# RobotTraceStopWatch.net
KiCad netlist of a schematic drawn in EAGLE
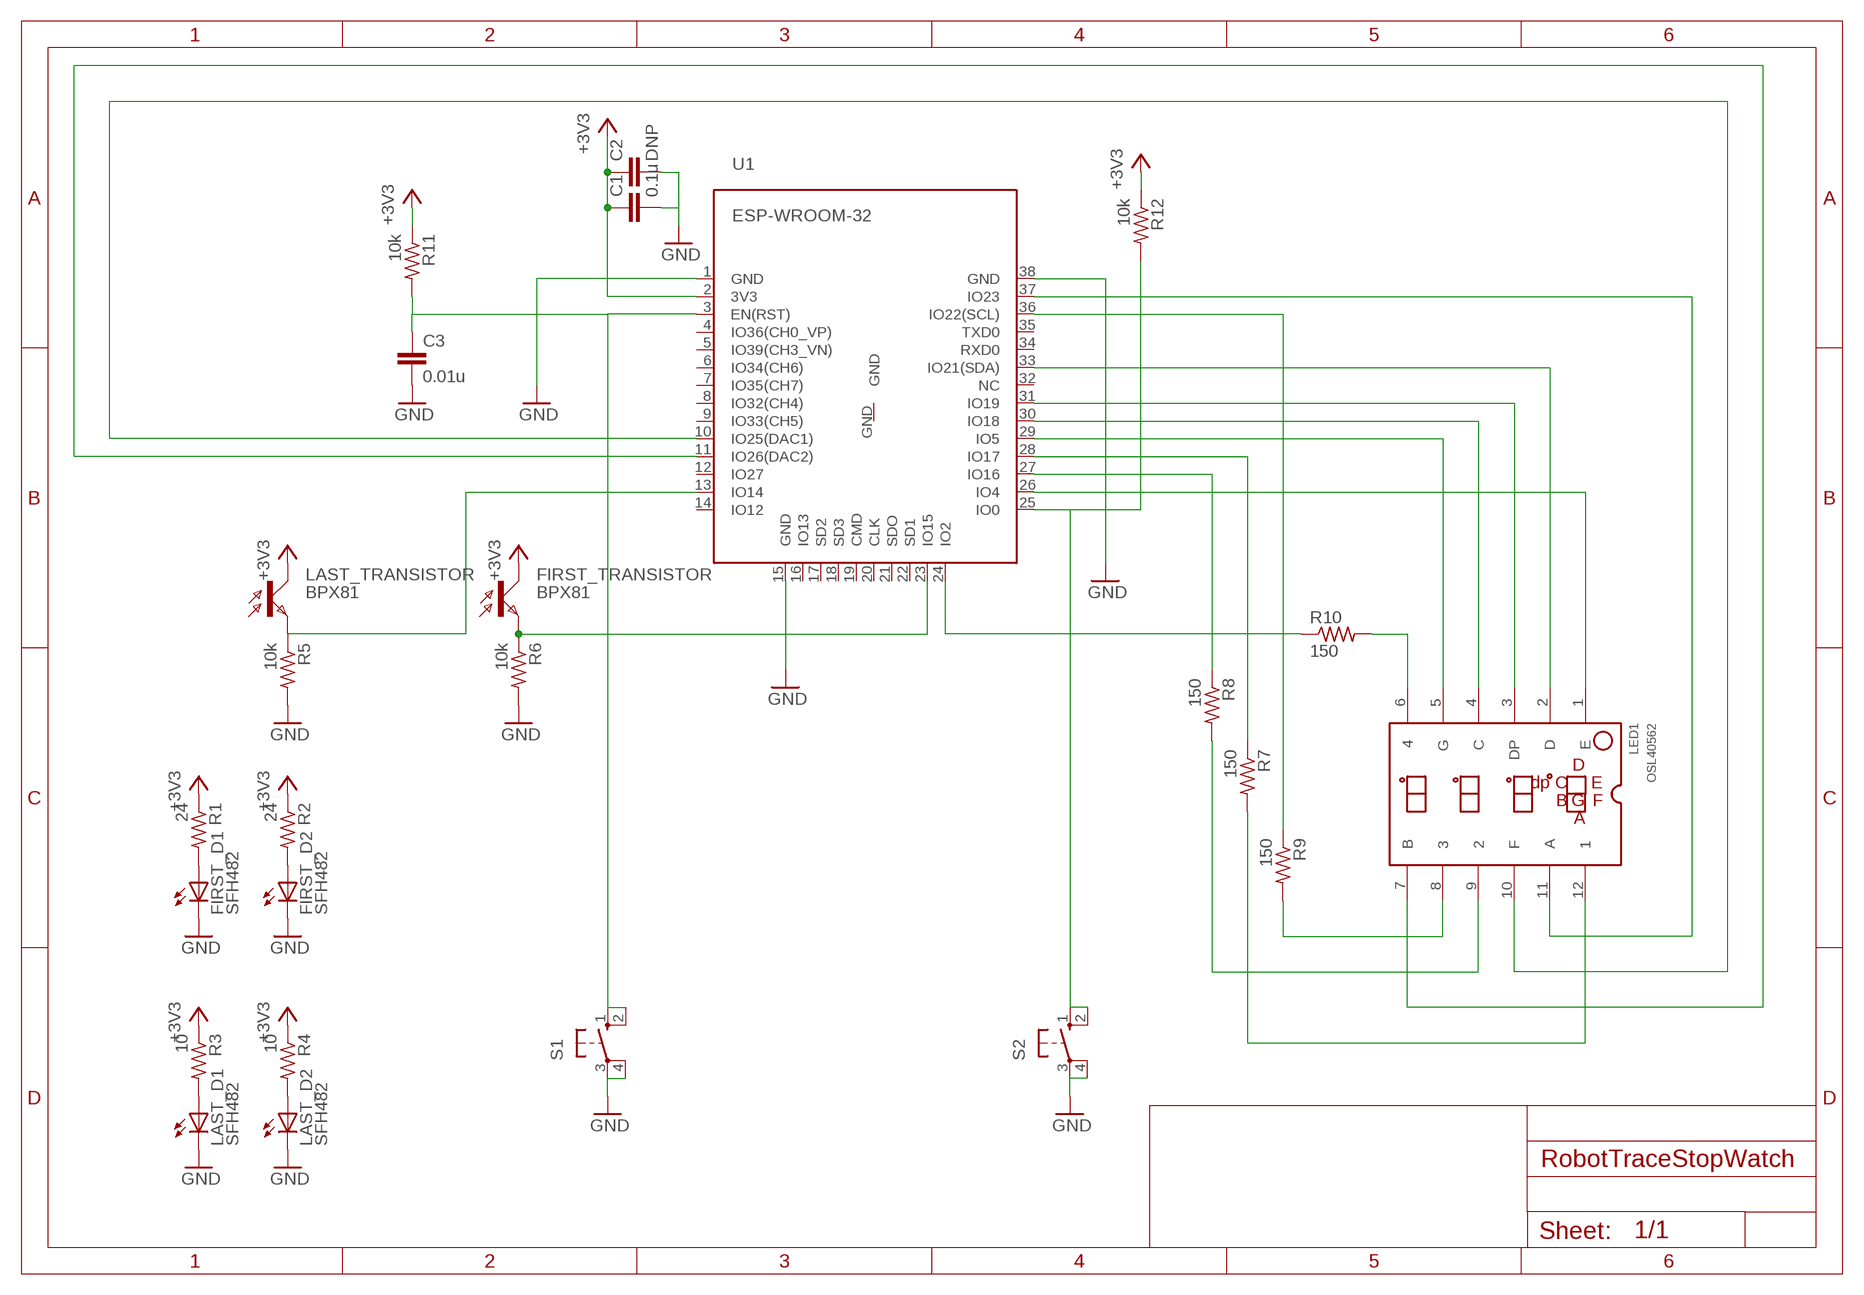
[diagram p0: schematic, sheet 1]

(export (version "E")
  (design (tool "Eeschema 10.0.6"))
  (components
    (comp (ref "C1")
      (value "0.1u")
      (footprint "eagle-import:C0805")
      (libsource (lib "eagle-import") (part "C"))
    )
    (comp (ref "C2")
      (value "DNP")
      (footprint "eagle-import:C0805")
      (libsource (lib "eagle-import") (part "C"))
    )
    (comp (ref "C3")
      (value "0.01u")
      (footprint "eagle-import:C0805")
      (libsource (lib "eagle-import") (part "C"))
    )
    (comp (ref "FIRST_D1")
      (value "SFH482")
      (footprint "eagle-import:SFH482")
      (libsource (lib "eagle-import") (part "SFH482"))
    )
    (comp (ref "FIRST_D2")
      (value "SFH482")
      (footprint "eagle-import:SFH482")
      (libsource (lib "eagle-import") (part "SFH482"))
    )
    (comp (ref "FIRST_TRANSISTOR")
      (value "BPX81")
      (footprint "eagle-import:BPX81")
      (libsource (lib "eagle-import") (part "BPX81"))
    )
    (comp (ref "LAST_D1")
      (value "SFH482")
      (footprint "eagle-import:SFH482")
      (libsource (lib "eagle-import") (part "SFH482"))
    )
    (comp (ref "LAST_D2")
      (value "SFH482")
      (footprint "eagle-import:SFH482")
      (libsource (lib "eagle-import") (part "SFH482"))
    )
    (comp (ref "LAST_TRANSISTOR")
      (value "BPX81")
      (footprint "eagle-import:BPX81")
      (libsource (lib "eagle-import") (part "BPX81"))
    )
    (comp (ref "LED1")
      (value "OSL40562")
      (footprint "eagle-import:OSL40562")
      (libsource (lib "eagle-import") (part "OSL40562"))
    )
    (comp (ref "R1")
      (value "24")
      (footprint "eagle-import:0204_7")
      (libsource (lib "eagle-import") (part "R-US_0204/7"))
    )
    (comp (ref "R2")
      (value "24")
      (footprint "eagle-import:0204_7")
      (libsource (lib "eagle-import") (part "R-US_0204/7"))
    )
    (comp (ref "R3")
      (value "10")
      (footprint "eagle-import:0204_7")
      (libsource (lib "eagle-import") (part "R-US_0204/7"))
    )
    (comp (ref "R4")
      (value "10")
      (footprint "eagle-import:0204_7")
      (libsource (lib "eagle-import") (part "R-US_0204/7"))
    )
    (comp (ref "R5")
      (value "10k")
      (footprint "eagle-import:0204_7")
      (libsource (lib "eagle-import") (part "R-US_0204/7"))
    )
    (comp (ref "R6")
      (value "10k")
      (footprint "eagle-import:0204_7")
      (libsource (lib "eagle-import") (part "R-US_0204/7"))
    )
    (comp (ref "R7")
      (value "150")
      (footprint "eagle-import:0204_7")
      (libsource (lib "eagle-import") (part "R-US_0204/7"))
    )
    (comp (ref "R8")
      (value "150")
      (footprint "eagle-import:0204_7")
      (libsource (lib "eagle-import") (part "R-US_0204/7"))
    )
    (comp (ref "R9")
      (value "150")
      (footprint "eagle-import:0204_7")
      (libsource (lib "eagle-import") (part "R-US_0204/7"))
    )
    (comp (ref "R10")
      (value "150")
      (footprint "eagle-import:0204_7")
      (libsource (lib "eagle-import") (part "R-US_0204/7"))
    )
    (comp (ref "R11")
      (value "10k")
      (footprint "eagle-import:0204_7")
      (libsource (lib "eagle-import") (part "R-US_0204/7"))
    )
    (comp (ref "R12")
      (value "10k")
      (footprint "eagle-import:0204_7")
      (libsource (lib "eagle-import") (part "R-US_0204/7"))
    )
    (comp (ref "S1")
      (value "10-XX")
      (footprint "eagle-import:B3F-10XX")
      (fields (field (name "MPN") "B3F-1000"))
      (libsource (lib "eagle-import") (part "10-XX"))
    )
    (comp (ref "S2")
      (value "10-XX")
      (footprint "eagle-import:B3F-10XX")
      (fields (field (name "MPN") "B3F-1000"))
      (libsource (lib "eagle-import") (part "10-XX"))
    )
    (comp (ref "U1")
      (value "ESP-WROOM-32")
      (footprint "eagle-import:ESP-WROOM-32")
      (libsource (lib "eagle-import") (part "ESP-WROOM-32"))
    )
  )
  (nets
    (net (code "1") (name "+3V3") (class "Default")
      (node (ref "C1") (pin "1") (pinfunction "1_1") (pintype "passive"))
      (node (ref "C2") (pin "1") (pinfunction "1_1") (pintype "passive"))
      (node (ref "FIRST_TRANSISTOR") (pin "C") (pinfunction "C_C") (pintype "passive"))
      (node (ref "LAST_TRANSISTOR") (pin "C") (pinfunction "C_C") (pintype "passive"))
      (node (ref "R1") (pin "1") (pinfunction "1_1") (pintype "passive"))
      (node (ref "R11") (pin "1") (pinfunction "1_1") (pintype "passive"))
      (node (ref "R12") (pin "1") (pinfunction "1_1") (pintype "passive"))
      (node (ref "R2") (pin "1") (pinfunction "1_1") (pintype "passive"))
      (node (ref "R3") (pin "1") (pinfunction "1_1") (pintype "passive"))
      (node (ref "R4") (pin "1") (pinfunction "1_1") (pintype "passive"))
      (node (ref "U1") (pin "2") (pinfunction "3V3_2") (pintype "bidirectional"))
    )
    (net (code "2") (name "GND") (class "Default")
      (node (ref "C1") (pin "2") (pinfunction "2_2") (pintype "passive"))
      (node (ref "C2") (pin "2") (pinfunction "2_2") (pintype "passive"))
      (node (ref "C3") (pin "2") (pinfunction "2_2") (pintype "passive"))
      (node (ref "FIRST_D1") (pin "K") (pinfunction "C_K") (pintype "passive"))
      (node (ref "FIRST_D2") (pin "K") (pinfunction "C_K") (pintype "passive"))
      (node (ref "LAST_D1") (pin "K") (pinfunction "C_K") (pintype "passive"))
      (node (ref "LAST_D2") (pin "K") (pinfunction "C_K") (pintype "passive"))
      (node (ref "R5") (pin "2") (pinfunction "2_2") (pintype "passive"))
      (node (ref "R6") (pin "2") (pinfunction "2_2") (pintype "passive"))
      (node (ref "S1") (pin "3") (pinfunction "P_3") (pintype "passive"))
      (node (ref "S1") (pin "4") (pinfunction "P1_4") (pintype "passive"))
      (node (ref "S2") (pin "3") (pinfunction "P_3") (pintype "passive"))
      (node (ref "S2") (pin "4") (pinfunction "P1_4") (pintype "passive"))
      (node (ref "U1") (pin "1") (pinfunction "GND_1") (pintype "bidirectional"))
      (node (ref "U1") (pin "15") (pinfunction "GND_15") (pintype "bidirectional"))
      (node (ref "U1") (pin "38") (pinfunction "GND_38") (pintype "bidirectional"))
    )
    (net (code "3") (name "Net-(FIRST_D1-PadA)") (class "Default")
      (node (ref "FIRST_D1") (pin "A") (pinfunction "A_A") (pintype "passive"))
      (node (ref "R1") (pin "2") (pinfunction "2_2") (pintype "passive"))
    )
    (net (code "4") (name "Net-(FIRST_D2-PadA)") (class "Default")
      (node (ref "FIRST_D2") (pin "A") (pinfunction "A_A") (pintype "passive"))
      (node (ref "R2") (pin "2") (pinfunction "2_2") (pintype "passive"))
    )
    (net (code "5") (name "Net-(LAST_D1-PadA)") (class "Default")
      (node (ref "LAST_D1") (pin "A") (pinfunction "A_A") (pintype "passive"))
      (node (ref "R3") (pin "2") (pinfunction "2_2") (pintype "passive"))
    )
    (net (code "6") (name "Net-(LAST_D2-PadA)") (class "Default")
      (node (ref "LAST_D2") (pin "A") (pinfunction "A_A") (pintype "passive"))
      (node (ref "R4") (pin "2") (pinfunction "2_2") (pintype "passive"))
    )
    (net (code "7") (name "Net-(LED1-1)") (class "Default")
      (node (ref "LED1") (pin "12") (pinfunction "1_12") (pintype "input"))
      (node (ref "R7") (pin "2") (pinfunction "2_2") (pintype "passive"))
    )
    (net (code "8") (name "Net-(LED1-2)") (class "Default")
      (node (ref "LED1") (pin "9") (pinfunction "2_9") (pintype "input"))
      (node (ref "R8") (pin "2") (pinfunction "2_2") (pintype "passive"))
    )
    (net (code "9") (name "Net-(LED1-3)") (class "Default")
      (node (ref "LED1") (pin "8") (pinfunction "3_8") (pintype "input"))
      (node (ref "R9") (pin "2") (pinfunction "2_2") (pintype "passive"))
    )
    (net (code "10") (name "Net-(LED1-4)") (class "Default")
      (node (ref "LED1") (pin "6") (pinfunction "4_6") (pintype "input"))
      (node (ref "R10") (pin "2") (pinfunction "2_2") (pintype "passive"))
    )
    (net (code "11") (name "Net-(LED1-A)") (class "Default")
      (node (ref "LED1") (pin "11") (pinfunction "A_11") (pintype "input"))
      (node (ref "U1") (pin "37") (pinfunction "IO23_37") (pintype "bidirectional"))
    )
    (net (code "12") (name "Net-(LED1-B)") (class "Default")
      (node (ref "LED1") (pin "7") (pinfunction "B_7") (pintype "input"))
      (node (ref "U1") (pin "11") (pinfunction "IO26(DAC2)_11") (pintype "bidirectional"))
    )
    (net (code "13") (name "Net-(LED1-C)") (class "Default")
      (node (ref "LED1") (pin "4") (pinfunction "C_4") (pintype "input"))
      (node (ref "U1") (pin "30") (pinfunction "IO18_30") (pintype "bidirectional"))
    )
    (net (code "14") (name "Net-(LED1-D)") (class "Default")
      (node (ref "LED1") (pin "2") (pinfunction "D_2") (pintype "input"))
      (node (ref "U1") (pin "33") (pinfunction "IO21(SDA)_33") (pintype "bidirectional"))
    )
    (net (code "15") (name "Net-(LED1-DP)") (class "Default")
      (node (ref "LED1") (pin "3") (pinfunction "DP_3") (pintype "input"))
      (node (ref "U1") (pin "31") (pinfunction "IO19_31") (pintype "bidirectional"))
    )
    (net (code "16") (name "Net-(LED1-E)") (class "Default")
      (node (ref "LED1") (pin "1") (pinfunction "E_1") (pintype "input"))
      (node (ref "U1") (pin "26") (pinfunction "IO4_26") (pintype "bidirectional"))
    )
    (net (code "17") (name "Net-(LED1-F)") (class "Default")
      (node (ref "LED1") (pin "10") (pinfunction "F_10") (pintype "input"))
      (node (ref "U1") (pin "10") (pinfunction "IO25(DAC1)_10") (pintype "bidirectional"))
    )
    (net (code "18") (name "Net-(LED1-G)") (class "Default")
      (node (ref "LED1") (pin "5") (pinfunction "G_5") (pintype "input"))
      (node (ref "U1") (pin "29") (pinfunction "IO5_29") (pintype "bidirectional"))
    )
    (net (code "19") (name "Net-(S1-S)") (class "Default")
      (node (ref "C3") (pin "1") (pinfunction "1_1") (pintype "passive"))
      (node (ref "R11") (pin "2") (pinfunction "2_2") (pintype "passive"))
      (node (ref "S1") (pin "1") (pinfunction "S_1") (pintype "passive"))
      (node (ref "S1") (pin "2") (pinfunction "S1_2") (pintype "passive"))
      (node (ref "U1") (pin "3") (pinfunction "EN(RST)_3") (pintype "bidirectional"))
    )
    (net (code "20") (name "Net-(S2-S)") (class "Default")
      (node (ref "R12") (pin "2") (pinfunction "2_2") (pintype "passive"))
      (node (ref "S2") (pin "1") (pinfunction "S_1") (pintype "passive"))
      (node (ref "S2") (pin "2") (pinfunction "S1_2") (pintype "passive"))
      (node (ref "U1") (pin "25") (pinfunction "IO0_25") (pintype "bidirectional"))
    )
    (net (code "21") (name "Net-(U1-IO2)") (class "Default")
      (node (ref "R10") (pin "1") (pinfunction "1_1") (pintype "passive"))
      (node (ref "U1") (pin "24") (pinfunction "IO2_24") (pintype "bidirectional"))
    )
    (net (code "22") (name "Net-(U1-IO14)") (class "Default")
      (node (ref "LAST_TRANSISTOR") (pin "E") (pinfunction "E_E") (pintype "passive"))
      (node (ref "R5") (pin "1") (pinfunction "1_1") (pintype "passive"))
      (node (ref "U1") (pin "13") (pinfunction "IO14_13") (pintype "bidirectional"))
    )
    (net (code "23") (name "Net-(U1-IO15)") (class "Default")
      (node (ref "FIRST_TRANSISTOR") (pin "E") (pinfunction "E_E") (pintype "passive"))
      (node (ref "R6") (pin "1") (pinfunction "1_1") (pintype "passive"))
      (node (ref "U1") (pin "23") (pinfunction "IO15_23") (pintype "bidirectional"))
    )
    (net (code "24") (name "Net-(U1-IO16)") (class "Default")
      (node (ref "R8") (pin "1") (pinfunction "1_1") (pintype "passive"))
      (node (ref "U1") (pin "27") (pinfunction "IO16_27") (pintype "bidirectional"))
    )
    (net (code "25") (name "Net-(U1-IO17)") (class "Default")
      (node (ref "R7") (pin "1") (pinfunction "1_1") (pintype "passive"))
      (node (ref "U1") (pin "28") (pinfunction "IO17_28") (pintype "bidirectional"))
    )
    (net (code "26") (name "Net-(U1-IO22(SCL))") (class "Default")
      (node (ref "R9") (pin "1") (pinfunction "1_1") (pintype "passive"))
      (node (ref "U1") (pin "36") (pinfunction "IO22(SCL)_36") (pintype "bidirectional"))
    )
    (net (code "27") (name "unconnected-(U1-CLK-Pad20)") (class "Default")
      (node (ref "U1") (pin "20") (pinfunction "CLK_20") (pintype "bidirectional"))
    )
    (net (code "28") (name "unconnected-(U1-CMD-Pad19)") (class "Default")
      (node (ref "U1") (pin "19") (pinfunction "CMD_19") (pintype "bidirectional"))
    )
    (net (code "29") (name "unconnected-(U1-IO12-Pad14)") (class "Default")
      (node (ref "U1") (pin "14") (pinfunction "IO12_14") (pintype "bidirectional"))
    )
    (net (code "30") (name "unconnected-(U1-IO13-Pad16)") (class "Default")
      (node (ref "U1") (pin "16") (pinfunction "IO13_16") (pintype "bidirectional"))
    )
    (net (code "31") (name "unconnected-(U1-IO27-Pad12)") (class "Default")
      (node (ref "U1") (pin "12") (pinfunction "IO27_12") (pintype "bidirectional"))
    )
    (net (code "32") (name "unconnected-(U1-IO32(CH4)-Pad8)") (class "Default")
      (node (ref "U1") (pin "8") (pinfunction "IO32(CH4)_8") (pintype "bidirectional"))
    )
    (net (code "33") (name "unconnected-(U1-IO33(CH5)-Pad9)") (class "Default")
      (node (ref "U1") (pin "9") (pinfunction "IO33(CH5)_9") (pintype "bidirectional"))
    )
    (net (code "34") (name "unconnected-(U1-IO34(CH6)-Pad6)") (class "Default")
      (node (ref "U1") (pin "6") (pinfunction "IO34(CH6)_6") (pintype "bidirectional"))
    )
    (net (code "35") (name "unconnected-(U1-IO35(CH7)-Pad7)") (class "Default")
      (node (ref "U1") (pin "7") (pinfunction "IO35(CH7)_7") (pintype "bidirectional"))
    )
    (net (code "36") (name "unconnected-(U1-IO36(CH0_VP)-Pad4)") (class "Default")
      (node (ref "U1") (pin "4") (pinfunction "IO36(CH0_VP)_4") (pintype "bidirectional"))
    )
    (net (code "37") (name "unconnected-(U1-IO39(CH3_VN)-Pad5)") (class "Default")
      (node (ref "U1") (pin "5") (pinfunction "IO39(CH3_VN)_5") (pintype "bidirectional"))
    )
    (net (code "38") (name "unconnected-(U1-NC-Pad32)") (class "Default")
      (node (ref "U1") (pin "32") (pinfunction "NC_32") (pintype "bidirectional"))
    )
    (net (code "39") (name "unconnected-(U1-PadGND)") (class "Default")
      (node (ref "U1") (pin "GND") (pinfunction "GND_GND") (pintype "bidirectional"))
    )
    (net (code "40") (name "unconnected-(U1-RXD0-Pad34)") (class "Default")
      (node (ref "U1") (pin "34") (pinfunction "RXD0_34") (pintype "bidirectional"))
    )
    (net (code "41") (name "unconnected-(U1-SD1-Pad22)") (class "Default")
      (node (ref "U1") (pin "22") (pinfunction "SD1_22") (pintype "bidirectional"))
    )
    (net (code "42") (name "unconnected-(U1-SD2-Pad17)") (class "Default")
      (node (ref "U1") (pin "17") (pinfunction "SD2_17") (pintype "bidirectional"))
    )
    (net (code "43") (name "unconnected-(U1-SD3-Pad18)") (class "Default")
      (node (ref "U1") (pin "18") (pinfunction "SD3_18") (pintype "bidirectional"))
    )
    (net (code "44") (name "unconnected-(U1-SDO-Pad21)") (class "Default")
      (node (ref "U1") (pin "21") (pinfunction "SDO_21") (pintype "bidirectional"))
    )
    (net (code "45") (name "unconnected-(U1-TXD0-Pad35)") (class "Default")
      (node (ref "U1") (pin "35") (pinfunction "TXD0_35") (pintype "bidirectional"))
    )
  )
)
